# SCNano-Geig.net
KiCad netlist of a schematic drawn in Altium Designer
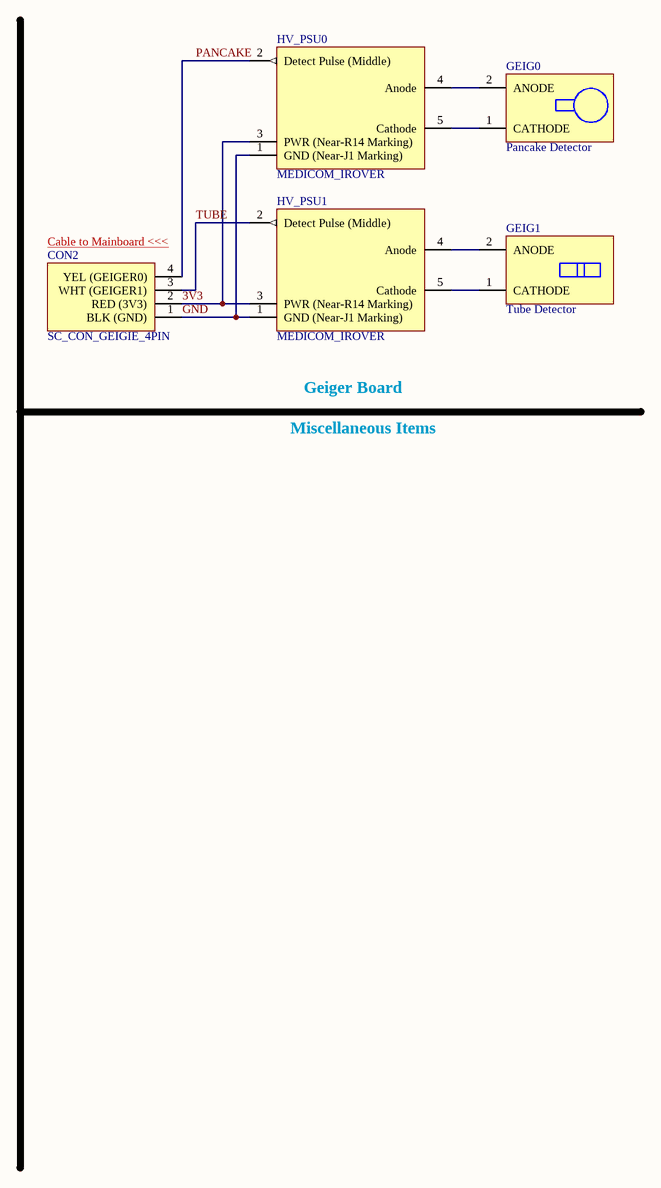
[diagram p0: SCNano-Geig.SchDoc]

(export (version "E")
  (design (tool "Eeschema 10.0.6"))
  (components
    (comp (ref "CON2")
      (value "SC_CON_GEIGIE_4PIN")
      (footprint "NSTECH 1125S")
      (description "Grove 4 Pin Connector Female T/H, labeled for Safecast Geiegie products")
      (fields
        (field (name "MANUFACTURER") "Grove")
        (field (name "MANUFACTURER PART NUMBER") "4 Pin Connector")
      )
      (libsource (lib "scnano-lib") (part "SC_CON_GEIGIE_4PIN"))
    )
    (comp (ref "GEIG0")
      (value "Pancake Detector")
      (description "LND 7318 Pancake Geiger Tube")
      (fields (field (name "MANUFACTURER") "LND") (field (name "MANUFACTURER PART NUMBER") "7317"))
      (libsource (lib "scnano-lib") (part "LND_7318"))
    )
    (comp (ref "GEIG1")
      (value "Tube Detector")
      (description "LND 7128 Energy-Compensated Geiger Tube")
      (fields (field (name "MANUFACTURER") "LND") (field (name "MANUFACTURER PART NUMBER") "7128"))
      (libsource (lib "scnano-lib") (part "LND_7128"))
    )
    (comp (ref "HV_PSU0")
      (value "MEDICOM_IROVER")
      (footprint "IROVER_HV")
      (description "International Medcom iRover High-Voltage Power Supply and Counter Module")
      (fields (field (name "MANUFACTURER") "Medicom") (field (name "MANUFACTURER PART NUMBER") "IRover PSU"))
      (libsource (lib "scnano-lib") (part "MEDICOM_IROVER"))
    )
    (comp (ref "HV_PSU1")
      (value "MEDICOM_IROVER")
      (footprint "IROVER_HV")
      (description "International Medcom iRover High-Voltage Power Supply and Counter Module")
      (fields (field (name "MANUFACTURER") "Medicom") (field (name "MANUFACTURER PART NUMBER") "IRover PSU"))
      (libsource (lib "scnano-lib") (part "MEDICOM_IROVER"))
    )
  )
  (nets
    (net (code "1") (name "/3V3") (class "Default")
      (node (ref "CON2") (pin "2") (pinfunction "RED_(3V3)_2") (pintype "passive"))
      (node (ref "HV_PSU0") (pin "3") (pinfunction "PWR_(Near-R14_Marking)_3") (pintype "passive"))
      (node (ref "HV_PSU1") (pin "3") (pinfunction "PWR_(Near-R14_Marking)_3") (pintype "passive"))
    )
    (net (code "2") (name "/GND") (class "Default")
      (node (ref "CON2") (pin "1") (pinfunction "BLK_(GND)_1") (pintype "passive"))
      (node (ref "HV_PSU0") (pin "1") (pinfunction "GND_(Near-J1_Marking)_1") (pintype "passive"))
      (node (ref "HV_PSU1") (pin "1") (pinfunction "GND_(Near-J1_Marking)_1") (pintype "passive"))
    )
    (net (code "3") (name "/PANCAKE") (class "Default")
      (node (ref "CON2") (pin "4") (pinfunction "YEL_(GEIGER0)_4") (pintype "passive"))
      (node (ref "HV_PSU0") (pin "2") (pinfunction "Detect_Pulse_(Middle)_2") (pintype "output"))
    )
    (net (code "4") (name "/TUBE") (class "Default")
      (node (ref "CON2") (pin "3") (pinfunction "WHT_(GEIGER1)_3") (pintype "passive"))
      (node (ref "HV_PSU1") (pin "2") (pinfunction "Detect_Pulse_(Middle)_2") (pintype "output"))
    )
    (net (code "5") (name "Net-(GEIG0-ANODE)") (class "Default")
      (node (ref "GEIG0") (pin "2") (pinfunction "ANODE_2") (pintype "power_in"))
      (node (ref "HV_PSU0") (pin "4") (pinfunction "Anode_4") (pintype "passive"))
    )
    (net (code "6") (name "Net-(GEIG0-CATHODE)") (class "Default")
      (node (ref "GEIG0") (pin "1") (pinfunction "CATHODE_1") (pintype "power_in"))
      (node (ref "HV_PSU0") (pin "5") (pinfunction "Cathode_5") (pintype "passive"))
    )
    (net (code "7") (name "Net-(GEIG1-ANODE)") (class "Default")
      (node (ref "GEIG1") (pin "2") (pinfunction "ANODE_2") (pintype "power_in"))
      (node (ref "HV_PSU1") (pin "4") (pinfunction "Anode_4") (pintype "passive"))
    )
    (net (code "8") (name "Net-(GEIG1-CATHODE)") (class "Default")
      (node (ref "GEIG1") (pin "1") (pinfunction "CATHODE_1") (pintype "power_in"))
      (node (ref "HV_PSU1") (pin "5") (pinfunction "Cathode_5") (pintype "passive"))
    )
  )
)
